# mk6.net
KiCad netlist of a schematic drawn in EAGLE
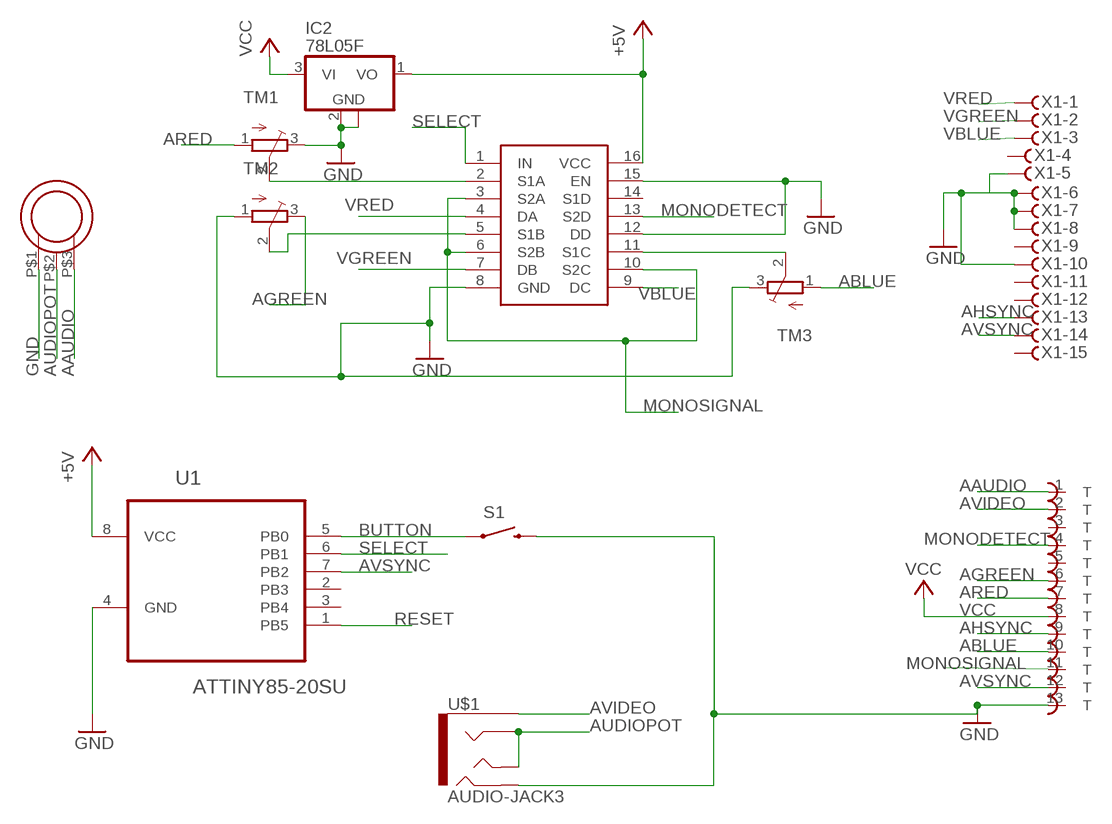
[diagram p0: schematic, sheet 1]

(export (version "E")
  (design (tool "Eeschema 10.0.6"))
  (components
    (comp (ref "ATARIOUT")
      (value "DIN13T")
      (footprint "eagle-import:ADADS")
      (libsource (lib "eagle-import") (part "DIN13T"))
    )
    (comp (ref "IC2")
      (value "78L05F")
      (footprint "eagle-import:SOT89")
      (libsource (lib "eagle-import") (part "78LF05"))
    )
    (comp (ref "S1")
      (value "SWITCH-MOMENTARY-2TACTILE-SWITCH-SMD-RIGHT-ANGLE")
      (footprint "eagle-import:TACTILE_SWITCH-SMD-RIGHT-ANGLE")
      (libsource (lib "eagle-import") (part "SWITCH-MOMENTARY-2TACTILE-SWITCH-SMD-RIGHT-ANGLE"))
    )
    (comp (ref "TM1")
      (value "TRIMPOTTC33X")
      (footprint "eagle-import:TC33X")
      (libsource (lib "eagle-import") (part "TRIMPOTTC33X"))
    )
    (comp (ref "TM2")
      (value "TRIMPOTTC33X")
      (footprint "eagle-import:TC33X")
      (libsource (lib "eagle-import") (part "TRIMPOTTC33X"))
    )
    (comp (ref "TM3")
      (value "TRIMPOTTC33X")
      (footprint "eagle-import:TC33X")
      (libsource (lib "eagle-import") (part "TRIMPOTTC33X"))
    )
    (comp (ref "TS5V330")
      (value "V330")
      (footprint "eagle-import:SOIC16N")
      (libsource (lib "eagle-import") (part "V330"))
    )
    (comp (ref "U$1")
      (value "AUDIO-JACK3")
      (footprint "eagle-import:AUDIO-JACK-TRRS-SMD")
      (libsource (lib "eagle-import") (part "AUDIO-JACK3"))
    )
    (comp (ref "U$2")
      (value "DB-1001N")
      (footprint "eagle-import:THUMB_POT")
      (libsource (lib "eagle-import") (part "DB-1001N"))
    )
    (comp (ref "U1")
      (value "ATTINY85-20SU")
      (footprint "eagle-import:SOIC127P798X216-8N")
      (libsource (lib "eagle-import") (part "ATTINY85-20SU"))
    )
    (comp (ref "X1")
      (value "F15HDVS")
      (footprint "eagle-import:HDF15V")
      (libsource (lib "eagle-import") (part "F15?SHDV"))
    )
  )
  (nets
    (net (code "1") (name "+5V") (class "Default")
      (node (ref "IC2") (pin "1") (pinfunction "VO_1") (pintype "passive"))
      (node (ref "TS5V330") (pin "16") (pinfunction "VCC_16") (pintype "bidirectional"))
      (node (ref "U1") (pin "8") (pinfunction "VCC_8") (pintype "power_in"))
    )
    (net (code "2") (name "/AAUDIO") (class "Default")
      (node (ref "ATARIOUT") (pin "1") (pinfunction "T_1") (pintype "passive"))
      (node (ref "U$2") (pin "P$3") (pinfunction "3_P$3") (pintype "bidirectional"))
    )
    (net (code "3") (name "/ABLUE") (class "Default")
      (node (ref "ATARIOUT") (pin "10") (pinfunction "T_10") (pintype "passive"))
      (node (ref "TM3") (pin "1") (pinfunction "A_1") (pintype "passive"))
    )
    (net (code "4") (name "/AGREEN") (class "Default")
      (node (ref "ATARIOUT") (pin "6") (pinfunction "T_6") (pintype "passive"))
      (node (ref "TM2") (pin "3") (pinfunction "E_3") (pintype "passive"))
    )
    (net (code "5") (name "/AHSYNC") (class "Default")
      (node (ref "ATARIOUT") (pin "9") (pinfunction "T_9") (pintype "passive"))
      (node (ref "X1") (pin "13") (pinfunction "F_13") (pintype "passive"))
    )
    (net (code "6") (name "/ARED") (class "Default")
      (node (ref "ATARIOUT") (pin "7") (pinfunction "T_7") (pintype "passive"))
      (node (ref "TM1") (pin "1") (pinfunction "A_1") (pintype "passive"))
    )
    (net (code "7") (name "/AUDIOPOT") (class "Default")
      (node (ref "U$1") (pin "RING1") (pinfunction "RING1_RING1") (pintype "bidirectional"))
      (node (ref "U$1") (pin "TIP") (pinfunction "TIP_TIP") (pintype "bidirectional"))
      (node (ref "U$2") (pin "P$2") (pinfunction "2_P$2") (pintype "bidirectional"))
    )
    (net (code "8") (name "/AVIDEO") (class "Default")
      (node (ref "ATARIOUT") (pin "2") (pinfunction "T_2") (pintype "passive"))
      (node (ref "U$1") (pin "EARTH") (pinfunction "EARTH_EARTH") (pintype "bidirectional"))
    )
    (net (code "9") (name "/AVSYNC") (class "Default")
      (node (ref "ATARIOUT") (pin "12") (pinfunction "T_12") (pintype "passive"))
      (node (ref "U1") (pin "7") (pinfunction "PB2_7") (pintype "bidirectional"))
      (node (ref "X1") (pin "14") (pinfunction "F_14") (pintype "passive"))
    )
    (net (code "10") (name "/BUTTON") (class "Default")
      (node (ref "S1") (pin "1") (pinfunction "1_1") (pintype "passive"))
      (node (ref "U1") (pin "5") (pinfunction "PB0_5") (pintype "bidirectional"))
    )
    (net (code "11") (name "/MONODETECT") (class "Default")
      (node (ref "ATARIOUT") (pin "4") (pinfunction "T_4") (pintype "passive"))
      (node (ref "TS5V330") (pin "13") (pinfunction "S2D_13") (pintype "bidirectional"))
    )
    (net (code "12") (name "/MONOSIGNAL") (class "Default")
      (node (ref "ATARIOUT") (pin "11") (pinfunction "T_11") (pintype "passive"))
      (node (ref "TS5V330") (pin "10") (pinfunction "S2C_10") (pintype "bidirectional"))
      (node (ref "TS5V330") (pin "3") (pinfunction "S2A_3") (pintype "bidirectional"))
      (node (ref "TS5V330") (pin "6") (pinfunction "S2B_6") (pintype "bidirectional"))
    )
    (net (code "13") (name "/RESET") (class "Default")
      (node (ref "U1") (pin "1") (pinfunction "PB5_1") (pintype "bidirectional"))
    )
    (net (code "14") (name "/SELECT") (class "Default")
      (node (ref "TS5V330") (pin "1") (pinfunction "IN_1") (pintype "bidirectional"))
      (node (ref "U1") (pin "6") (pinfunction "PB1_6") (pintype "bidirectional"))
    )
    (net (code "15") (name "/VBLUE") (class "Default")
      (node (ref "TS5V330") (pin "9") (pinfunction "DC_9") (pintype "bidirectional"))
      (node (ref "X1") (pin "3") (pinfunction "F_3") (pintype "passive"))
    )
    (net (code "16") (name "/VGREEN") (class "Default")
      (node (ref "TS5V330") (pin "7") (pinfunction "DB_7") (pintype "bidirectional"))
      (node (ref "X1") (pin "2") (pinfunction "F_2") (pintype "passive"))
    )
    (net (code "17") (name "/VRED") (class "Default")
      (node (ref "TS5V330") (pin "4") (pinfunction "DA_4") (pintype "bidirectional"))
      (node (ref "X1") (pin "1") (pinfunction "F_1") (pintype "passive"))
    )
    (net (code "18") (name "GND") (class "Default")
      (node (ref "ATARIOUT") (pin "13") (pinfunction "T_13") (pintype "passive"))
      (node (ref "IC2") (pin "2") (pinfunction "GND_2") (pintype "passive"))
      (node (ref "IC2") (pin "2@1") (pinfunction "GND_2@1") (pintype "passive"))
      (node (ref "S1") (pin "2") (pinfunction "2_2") (pintype "passive"))
      (node (ref "TM1") (pin "3") (pinfunction "E_3") (pintype "passive"))
      (node (ref "TM2") (pin "1") (pinfunction "A_1") (pintype "passive"))
      (node (ref "TM3") (pin "3") (pinfunction "E_3") (pintype "passive"))
      (node (ref "TS5V330") (pin "12") (pinfunction "DD_12") (pintype "bidirectional"))
      (node (ref "TS5V330") (pin "15") (pinfunction "EN_15") (pintype "bidirectional"))
      (node (ref "TS5V330") (pin "8") (pinfunction "GND_8") (pintype "bidirectional"))
      (node (ref "U$1") (pin "RING2") (pinfunction "RING2_RING2") (pintype "bidirectional"))
      (node (ref "U$2") (pin "P$1") (pinfunction "1_P$1") (pintype "bidirectional"))
      (node (ref "U1") (pin "4") (pinfunction "GND_4") (pintype "passive"))
      (node (ref "X1") (pin "10") (pinfunction "F_10") (pintype "passive"))
      (node (ref "X1") (pin "5") (pinfunction "F_5") (pintype "passive"))
      (node (ref "X1") (pin "6") (pinfunction "F_6") (pintype "passive"))
      (node (ref "X1") (pin "7") (pinfunction "F_7") (pintype "passive"))
      (node (ref "X1") (pin "8") (pinfunction "F_8") (pintype "passive"))
    )
    (net (code "19") (name "Net-(TM1-S)") (class "Default")
      (node (ref "TM1") (pin "2") (pinfunction "S_2") (pintype "passive"))
      (node (ref "TS5V330") (pin "2") (pinfunction "S1A_2") (pintype "bidirectional"))
    )
    (net (code "20") (name "Net-(TM2-S)") (class "Default")
      (node (ref "TM2") (pin "2") (pinfunction "S_2") (pintype "passive"))
      (node (ref "TS5V330") (pin "5") (pinfunction "S1B_5") (pintype "bidirectional"))
    )
    (net (code "21") (name "Net-(TM3-S)") (class "Default")
      (node (ref "TM3") (pin "2") (pinfunction "S_2") (pintype "passive"))
      (node (ref "TS5V330") (pin "11") (pinfunction "S1C_11") (pintype "bidirectional"))
    )
    (net (code "22") (name "VCC") (class "Default")
      (node (ref "ATARIOUT") (pin "8") (pinfunction "T_8") (pintype "passive"))
      (node (ref "IC2") (pin "3") (pinfunction "VI_3") (pintype "input"))
    )
    (net (code "23") (name "unconnected-(ATARIOUTG-T-Pad3)") (class "Default")
      (node (ref "ATARIOUT") (pin "3") (pinfunction "T_3") (pintype "passive"))
    )
    (net (code "24") (name "unconnected-(ATARIOUTI-T-Pad5)") (class "Default")
      (node (ref "ATARIOUT") (pin "5") (pinfunction "T_5") (pintype "passive"))
    )
    (net (code "25") (name "unconnected-(TS5V330-S1D-Pad14)") (class "Default")
      (node (ref "TS5V330") (pin "14") (pinfunction "S1D_14") (pintype "bidirectional"))
    )
    (net (code "26") (name "unconnected-(U1-PB3-Pad2)") (class "Default")
      (node (ref "U1") (pin "2") (pinfunction "PB3_2") (pintype "bidirectional"))
    )
    (net (code "27") (name "unconnected-(U1-PB4-Pad3)") (class "Default")
      (node (ref "U1") (pin "3") (pinfunction "PB4_3") (pintype "bidirectional"))
    )
    (net (code "28") (name "unconnected-(X1C-F-Pad11)") (class "Default")
      (node (ref "X1") (pin "11") (pinfunction "F_11") (pintype "passive"))
    )
    (net (code "29") (name "unconnected-(X1D-F-Pad12)") (class "Default")
      (node (ref "X1") (pin "12") (pinfunction "F_12") (pintype "passive"))
    )
    (net (code "30") (name "unconnected-(X1G-F-Pad15)") (class "Default")
      (node (ref "X1") (pin "15") (pinfunction "F_15") (pintype "passive"))
    )
    (net (code "31") (name "unconnected-(X1J-F-Pad4)") (class "Default")
      (node (ref "X1") (pin "4") (pinfunction "F_4") (pintype "passive"))
    )
    (net (code "32") (name "unconnected-(X1O-F-Pad9)") (class "Default")
      (node (ref "X1") (pin "9") (pinfunction "F_9") (pintype "passive"))
    )
  )
)
